# board_single_full1.net
KiCad netlist of a schematic drawn in EAGLE
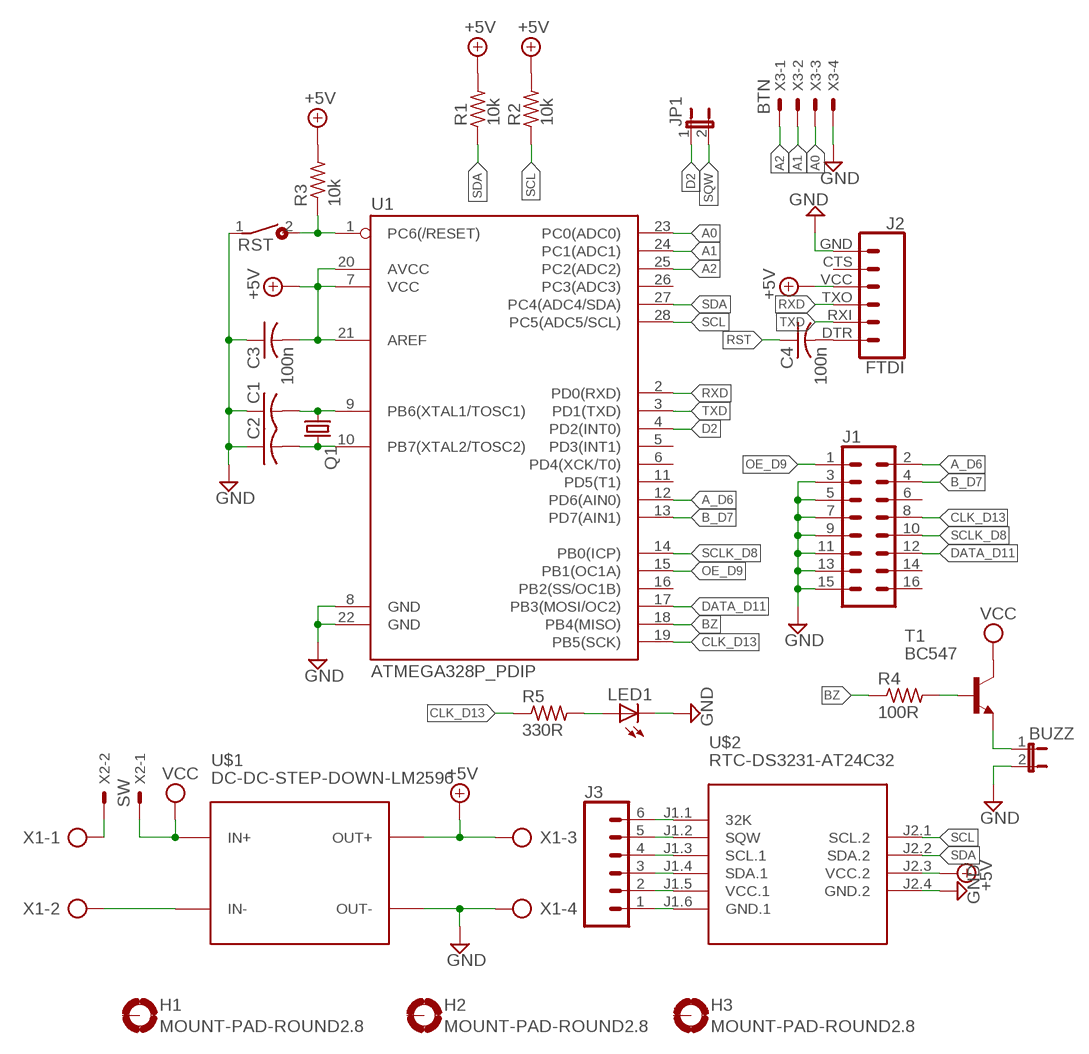
[diagram p0: schematic, sheet 1]

(export (version "E")
  (design (tool "Eeschema 10.0.6"))
  (components
    (comp (ref "BUZZ")
      (value "JP1E")
      (footprint "eagle-import:JP1")
      (libsource (lib "eagle-import") (part "JP1E"))
    )
    (comp (ref "C1")
      (value "C-USC0603K")
      (footprint "eagle-import:C0603K")
      (libsource (lib "eagle-import") (part "C-USC0603K"))
    )
    (comp (ref "C2")
      (value "C-USC0603K")
      (footprint "eagle-import:C0603K")
      (libsource (lib "eagle-import") (part "C-USC0603K"))
    )
    (comp (ref "C3")
      (value "100n")
      (footprint "eagle-import:C0603K")
      (libsource (lib "eagle-import") (part "C-USC0603K"))
    )
    (comp (ref "C4")
      (value "100n")
      (footprint "eagle-import:C0603K")
      (libsource (lib "eagle-import") (part "C-USC0603K"))
    )
    (comp (ref "H1")
      (value "MOUNT-PAD-ROUND2.8")
      (footprint "eagle-import:2,8-PAD")
      (libsource (lib "eagle-import") (part "MOUNT-PAD-ROUND2.8"))
    )
    (comp (ref "H2")
      (value "MOUNT-PAD-ROUND2.8")
      (footprint "eagle-import:2,8-PAD")
      (libsource (lib "eagle-import") (part "MOUNT-PAD-ROUND2.8"))
    )
    (comp (ref "H3")
      (value "MOUNT-PAD-ROUND2.8")
      (footprint "eagle-import:2,8-PAD")
      (libsource (lib "eagle-import") (part "MOUNT-PAD-ROUND2.8"))
    )
    (comp (ref "J1")
      (value "CONN_08X2_SHROUD")
      (footprint "eagle-import:2X8-SHROUDED_LOCK")
      (libsource (lib "eagle-import") (part "CONN_08X2_SHROUD"))
    )
    (comp (ref "J2")
      (value "FTDI")
      (footprint "eagle-import:FTDI_BASIC")
      (libsource (lib "eagle-import") (part "6_PIN_SERIAL_CABLEPTH"))
    )
    (comp (ref "J3")
      (value "CONN_06NO_SILK_FEMALE_PTH")
      (footprint "eagle-import:1X06_NO_SILK")
      (libsource (lib "eagle-import") (part "CONN_06NO_SILK_FEMALE_PTH"))
    )
    (comp (ref "JP1")
      (value "JP1E")
      (footprint "eagle-import:JP1")
      (libsource (lib "eagle-import") (part "JP1E"))
    )
    (comp (ref "LED1")
      (value "LED3MM")
      (footprint "eagle-import:LED3MM")
      (libsource (lib "eagle-import") (part "LED3MM"))
    )
    (comp (ref "Q1")
      (value "CRYSTALHC49U-V")
      (footprint "eagle-import:HC49U-V")
      (libsource (lib "eagle-import") (part "CRYSTALHC49U-V"))
    )
    (comp (ref "R1")
      (value "10k")
      (footprint "eagle-import:0207_7")
      (libsource (lib "eagle-import") (part "resistor_R-US_0207/7"))
    )
    (comp (ref "R2")
      (value "10k")
      (footprint "eagle-import:0207_7")
      (libsource (lib "eagle-import") (part "resistor_R-US_0207/7"))
    )
    (comp (ref "R3")
      (value "10k")
      (footprint "eagle-import:R0603")
      (libsource (lib "eagle-import") (part "R-US_R0603"))
    )
    (comp (ref "R4")
      (value "100R")
      (footprint "eagle-import:R0603")
      (libsource (lib "eagle-import") (part "R-US_R0603"))
    )
    (comp (ref "R5")
      (value "330R")
      (footprint "eagle-import:R0603")
      (libsource (lib "eagle-import") (part "R-US_R0603"))
    )
    (comp (ref "RST")
      (value "DS01E")
      (footprint "eagle-import:DS-01")
      (libsource (lib "eagle-import") (part "DS01E"))
    )
    (comp (ref "T1")
      (value "BC547")
      (footprint "eagle-import:TO92")
      (libsource (lib "eagle-import") (part "BC547"))
    )
    (comp (ref "U$1")
      (value "DC-DC-STEP-DOWN-LM2596")
      (footprint "eagle-import:DC-DC-STEP-DOWN-LM2596")
      (libsource (lib "eagle-import") (part "DC-DC-STEP-DOWN-LM2596"))
    )
    (comp (ref "U$2")
      (value "RTC-DS3231-AT24C32")
      (footprint "eagle-import:RTC-DS3231-AT24C32")
      (libsource (lib "eagle-import") (part "RTC-DS3231-AT24C32"))
    )
    (comp (ref "U1")
      (value "ATMEGA328P_PDIP")
      (footprint "eagle-import:DIL28-3")
      (libsource (lib "eagle-import") (part "ATMEGA328P_PDIP"))
    )
    (comp (ref "X1")
      (value "AK500/4")
      (footprint "eagle-import:AK500_4")
      (libsource (lib "eagle-import") (part "AK500/4"))
    )
    (comp (ref "X2")
      (value "SW")
      (footprint "eagle-import:JST-XH-02-PACKAGE-LONG-PAD")
      (libsource (lib "eagle-import") (part "JST-XH-02-PIN-LONG-PAD"))
    )
    (comp (ref "X3")
      (value "BTN")
      (footprint "eagle-import:JST-XH-04-PACKAGE-LONG-PAD")
      (libsource (lib "eagle-import") (part "JST-XH-04-PIN-LONG-PAD"))
    )
  )
  (nets
    (net (code "1") (name "+5V") (class "Default")
      (node (ref "C3") (pin "2") (pinfunction "2_2") (pintype "passive"))
      (node (ref "J2") (pin "VCC") (pinfunction "4_VCC") (pintype "passive"))
      (node (ref "R1") (pin "2") (pinfunction "2_2") (pintype "passive"))
      (node (ref "R2") (pin "2") (pinfunction "2_2") (pintype "passive"))
      (node (ref "R3") (pin "2") (pinfunction "2_2") (pintype "passive"))
      (node (ref "U$1") (pin "OUT+") (pinfunction "OUT+_OUT+") (pintype "bidirectional"))
      (node (ref "U$2") (pin "J2.3") (pinfunction "VCC.2_J2.3") (pintype "power_in"))
      (node (ref "U1") (pin "20") (pinfunction "AVCC_20") (pintype "bidirectional"))
      (node (ref "U1") (pin "21") (pinfunction "AREF_21") (pintype "bidirectional"))
      (node (ref "U1") (pin "7") (pinfunction "VCC_7") (pintype "bidirectional"))
      (node (ref "X1") (pin "3") (pinfunction "KL_3") (pintype "passive"))
    )
    (net (code "2") (name "A0") (class "Default")
      (node (ref "U1") (pin "23") (pinfunction "PC0(ADC0)_23") (pintype "bidirectional"))
      (node (ref "X3") (pin "3") (pinfunction "S_3") (pintype "passive"))
    )
    (net (code "3") (name "A1") (class "Default")
      (node (ref "U1") (pin "24") (pinfunction "PC1(ADC1)_24") (pintype "bidirectional"))
      (node (ref "X3") (pin "2") (pinfunction "S_2") (pintype "passive"))
    )
    (net (code "4") (name "A2") (class "Default")
      (node (ref "U1") (pin "25") (pinfunction "PC2(ADC2)_25") (pintype "bidirectional"))
      (node (ref "X3") (pin "1") (pinfunction "S_1") (pintype "passive"))
    )
    (net (code "5") (name "A_D6") (class "Default")
      (node (ref "J1") (pin "2") (pinfunction "2_2") (pintype "passive"))
      (node (ref "U1") (pin "12") (pinfunction "PD6(AIN0)_12") (pintype "bidirectional"))
    )
    (net (code "6") (name "BZ") (class "Default")
      (node (ref "R4") (pin "1") (pinfunction "1_1") (pintype "passive"))
      (node (ref "U1") (pin "18") (pinfunction "PB4(MISO)_18") (pintype "bidirectional"))
    )
    (net (code "7") (name "B_D7") (class "Default")
      (node (ref "J1") (pin "4") (pinfunction "4_4") (pintype "passive"))
      (node (ref "U1") (pin "13") (pinfunction "PD7(AIN1)_13") (pintype "bidirectional"))
    )
    (net (code "8") (name "CLK_D13") (class "Default")
      (node (ref "J1") (pin "8") (pinfunction "8_8") (pintype "passive"))
      (node (ref "R5") (pin "1") (pinfunction "1_1") (pintype "passive"))
      (node (ref "U1") (pin "19") (pinfunction "PB5(SCK)_19") (pintype "bidirectional"))
    )
    (net (code "9") (name "D2") (class "Default")
      (node (ref "JP1") (pin "1") (pinfunction "1_1") (pintype "passive"))
      (node (ref "U1") (pin "4") (pinfunction "PD2(INT0)_4") (pintype "bidirectional"))
    )
    (net (code "10") (name "DATA_D11") (class "Default")
      (node (ref "J1") (pin "12") (pinfunction "12_12") (pintype "passive"))
      (node (ref "U1") (pin "17") (pinfunction "PB3(MOSI/OC2)_17") (pintype "bidirectional"))
    )
    (net (code "11") (name "GND") (class "Default")
      (node (ref "BUZZ") (pin "2") (pinfunction "2_2") (pintype "passive"))
      (node (ref "C1") (pin "1") (pinfunction "1_1") (pintype "passive"))
      (node (ref "C2") (pin "1") (pinfunction "1_1") (pintype "passive"))
      (node (ref "C3") (pin "1") (pinfunction "1_1") (pintype "passive"))
      (node (ref "J1") (pin "11") (pinfunction "11_11") (pintype "passive"))
      (node (ref "J1") (pin "13") (pinfunction "13_13") (pintype "passive"))
      (node (ref "J1") (pin "15") (pinfunction "15_15") (pintype "passive"))
      (node (ref "J1") (pin "3") (pinfunction "3_3") (pintype "passive"))
      (node (ref "J1") (pin "5") (pinfunction "5_5") (pintype "passive"))
      (node (ref "J1") (pin "7") (pinfunction "7_7") (pintype "passive"))
      (node (ref "J1") (pin "9") (pinfunction "9_9") (pintype "passive"))
      (node (ref "J2") (pin "GND") (pinfunction "6_GND") (pintype "passive"))
      (node (ref "LED1") (pin "K") (pinfunction "C_K") (pintype "passive"))
      (node (ref "RST") (pin "1") (pinfunction "1_1") (pintype "passive"))
      (node (ref "U$1") (pin "OUT-") (pinfunction "OUT-_OUT-") (pintype "bidirectional"))
      (node (ref "U$2") (pin "J2.4") (pinfunction "GND.2_J2.4") (pintype "power_in"))
      (node (ref "U1") (pin "22") (pinfunction "GND_22") (pintype "bidirectional"))
      (node (ref "U1") (pin "8") (pinfunction "GND_8") (pintype "bidirectional"))
      (node (ref "X1") (pin "4") (pinfunction "KL_4") (pintype "passive"))
      (node (ref "X3") (pin "4") (pinfunction "S_4") (pintype "passive"))
    )
    (net (code "12") (name "Net-(J2-1)") (class "Default")
      (node (ref "C4") (pin "2") (pinfunction "2_2") (pintype "passive"))
      (node (ref "J2") (pin "DTR") (pinfunction "1_DTR") (pintype "passive"))
    )
    (net (code "13") (name "Net-(LED1-PadA)") (class "Default")
      (node (ref "LED1") (pin "A") (pinfunction "A_A") (pintype "passive"))
      (node (ref "R5") (pin "2") (pinfunction "2_2") (pintype "passive"))
    )
    (net (code "14") (name "Net-(T1-B)") (class "Default")
      (node (ref "R4") (pin "2") (pinfunction "2_2") (pintype "passive"))
      (node (ref "T1") (pin "2") (pinfunction "B_2") (pintype "passive"))
    )
    (net (code "15") (name "Net-(T1-E)") (class "Default")
      (node (ref "BUZZ") (pin "1") (pinfunction "1_1") (pintype "passive"))
      (node (ref "T1") (pin "1") (pinfunction "E_1") (pintype "passive"))
    )
    (net (code "16") (name "Net-(U$2-32K)") (class "Default")
      (node (ref "J3") (pin "6") (pinfunction "6_6") (pintype "passive"))
      (node (ref "U$2") (pin "J1.1") (pinfunction "32K_J1.1") (pintype "bidirectional"))
    )
    (net (code "17") (name "Net-(U$2-GND.1)") (class "Default")
      (node (ref "J3") (pin "1") (pinfunction "1_1") (pintype "passive"))
      (node (ref "U$2") (pin "J1.6") (pinfunction "GND.1_J1.6") (pintype "power_in"))
    )
    (net (code "18") (name "Net-(U$2-SCL.1)") (class "Default")
      (node (ref "J3") (pin "4") (pinfunction "4_4") (pintype "passive"))
      (node (ref "U$2") (pin "J1.3") (pinfunction "SCL.1_J1.3") (pintype "bidirectional"))
    )
    (net (code "19") (name "Net-(U$2-SDA.1)") (class "Default")
      (node (ref "J3") (pin "3") (pinfunction "3_3") (pintype "passive"))
      (node (ref "U$2") (pin "J1.4") (pinfunction "SDA.1_J1.4") (pintype "bidirectional"))
    )
    (net (code "20") (name "Net-(U$2-VCC.1)") (class "Default")
      (node (ref "J3") (pin "2") (pinfunction "2_2") (pintype "passive"))
      (node (ref "U$2") (pin "J1.5") (pinfunction "VCC.1_J1.5") (pintype "power_in"))
    )
    (net (code "21") (name "Net-(U1-PB6(XTAL1{slash}TOSC1))") (class "Default")
      (node (ref "C1") (pin "2") (pinfunction "2_2") (pintype "passive"))
      (node (ref "Q1") (pin "1") (pinfunction "1_1") (pintype "passive"))
      (node (ref "U1") (pin "9") (pinfunction "PB6(XTAL1/TOSC1)_9") (pintype "bidirectional"))
    )
    (net (code "22") (name "Net-(U1-PB7(XTAL2{slash}TOSC2))") (class "Default")
      (node (ref "C2") (pin "2") (pinfunction "2_2") (pintype "passive"))
      (node (ref "Q1") (pin "2") (pinfunction "2_2") (pintype "passive"))
      (node (ref "U1") (pin "10") (pinfunction "PB7(XTAL2/TOSC2)_10") (pintype "bidirectional"))
    )
    (net (code "23") (name "Net-(X1A-KL)") (class "Default")
      (node (ref "X1") (pin "1") (pinfunction "KL_1") (pintype "passive"))
      (node (ref "X2") (pin "2") (pinfunction "S_2") (pintype "passive"))
    )
    (net (code "24") (name "Net-(X1B-KL)") (class "Default")
      (node (ref "U$1") (pin "IN-") (pinfunction "IN-_IN-") (pintype "bidirectional"))
      (node (ref "X1") (pin "2") (pinfunction "KL_2") (pintype "passive"))
    )
    (net (code "25") (name "OE_D9") (class "Default")
      (node (ref "J1") (pin "1") (pinfunction "1_1") (pintype "passive"))
      (node (ref "U1") (pin "15") (pinfunction "PB1(OC1A)_15") (pintype "bidirectional"))
    )
    (net (code "26") (name "RST") (class "Default")
      (node (ref "C4") (pin "1") (pinfunction "1_1") (pintype "passive"))
      (node (ref "R3") (pin "1") (pinfunction "1_1") (pintype "passive"))
      (node (ref "RST") (pin "2") (pinfunction "2_2") (pintype "passive"))
      (node (ref "U1") (pin "1") (pinfunction "PC6(/RESET)_1") (pintype "bidirectional"))
    )
    (net (code "27") (name "RXD") (class "Default")
      (node (ref "J2") (pin "TXO") (pinfunction "3_TXO") (pintype "passive"))
      (node (ref "U1") (pin "2") (pinfunction "PD0(RXD)_2") (pintype "bidirectional"))
    )
    (net (code "28") (name "SCL") (class "Default")
      (node (ref "R2") (pin "1") (pinfunction "1_1") (pintype "passive"))
      (node (ref "U$2") (pin "J2.1") (pinfunction "SCL.2_J2.1") (pintype "bidirectional"))
      (node (ref "U1") (pin "28") (pinfunction "PC5(ADC5/SCL)_28") (pintype "bidirectional"))
    )
    (net (code "29") (name "SCLK_D8") (class "Default")
      (node (ref "J1") (pin "10") (pinfunction "10_10") (pintype "passive"))
      (node (ref "U1") (pin "14") (pinfunction "PB0(ICP)_14") (pintype "bidirectional"))
    )
    (net (code "30") (name "SDA") (class "Default")
      (node (ref "R1") (pin "1") (pinfunction "1_1") (pintype "passive"))
      (node (ref "U$2") (pin "J2.2") (pinfunction "SDA.2_J2.2") (pintype "bidirectional"))
      (node (ref "U1") (pin "27") (pinfunction "PC4(ADC4/SDA)_27") (pintype "bidirectional"))
    )
    (net (code "31") (name "SQW") (class "Default")
      (node (ref "J3") (pin "5") (pinfunction "5_5") (pintype "passive"))
      (node (ref "JP1") (pin "2") (pinfunction "2_2") (pintype "passive"))
      (node (ref "U$2") (pin "J1.2") (pinfunction "SQW_J1.2") (pintype "bidirectional"))
    )
    (net (code "32") (name "TXD") (class "Default")
      (node (ref "J2") (pin "RXI") (pinfunction "2_RXI") (pintype "passive"))
      (node (ref "U1") (pin "3") (pinfunction "PD1(TXD)_3") (pintype "bidirectional"))
    )
    (net (code "33") (name "VCC") (class "Default")
      (node (ref "T1") (pin "3") (pinfunction "C_3") (pintype "passive"))
      (node (ref "U$1") (pin "IN+") (pinfunction "IN+_IN+") (pintype "bidirectional"))
      (node (ref "X2") (pin "1") (pinfunction "S_1") (pintype "passive"))
    )
    (net (code "34") (name "unconnected-(H1-MOUNT-PadB2,8)") (class "Default")
      (node (ref "H1") (pin "B2,8") (pinfunction "MOUNT_B2,8") (pintype "passive"))
    )
    (net (code "35") (name "unconnected-(H2-MOUNT-PadB2,8)") (class "Default")
      (node (ref "H2") (pin "B2,8") (pinfunction "MOUNT_B2,8") (pintype "passive"))
    )
    (net (code "36") (name "unconnected-(H3-MOUNT-PadB2,8)") (class "Default")
      (node (ref "H3") (pin "B2,8") (pinfunction "MOUNT_B2,8") (pintype "passive"))
    )
    (net (code "37") (name "unconnected-(J1-Pad6)") (class "Default")
      (node (ref "J1") (pin "6") (pinfunction "6_6") (pintype "passive"))
    )
    (net (code "38") (name "unconnected-(J1-Pad14)") (class "Default")
      (node (ref "J1") (pin "14") (pinfunction "14_14") (pintype "passive"))
    )
    (net (code "39") (name "unconnected-(J1-Pad16)") (class "Default")
      (node (ref "J1") (pin "16") (pinfunction "16_16") (pintype "passive"))
    )
    (net (code "40") (name "unconnected-(J2-5-PadCTS)") (class "Default")
      (node (ref "J2") (pin "CTS") (pinfunction "5_CTS") (pintype "passive"))
    )
    (net (code "41") (name "unconnected-(U1-PB2(SS{slash}OC1B)-Pad16)") (class "Default")
      (node (ref "U1") (pin "16") (pinfunction "PB2(SS/OC1B)_16") (pintype "bidirectional"))
    )
    (net (code "42") (name "unconnected-(U1-PC3(ADC3)-Pad26)") (class "Default")
      (node (ref "U1") (pin "26") (pinfunction "PC3(ADC3)_26") (pintype "bidirectional"))
    )
    (net (code "43") (name "unconnected-(U1-PD3(INT1)-Pad5)") (class "Default")
      (node (ref "U1") (pin "5") (pinfunction "PD3(INT1)_5") (pintype "bidirectional"))
    )
    (net (code "44") (name "unconnected-(U1-PD4(XCK{slash}T0)-Pad6)") (class "Default")
      (node (ref "U1") (pin "6") (pinfunction "PD4(XCK/T0)_6") (pintype "bidirectional"))
    )
    (net (code "45") (name "unconnected-(U1-PD5(T1)-Pad11)") (class "Default")
      (node (ref "U1") (pin "11") (pinfunction "PD5(T1)_11") (pintype "bidirectional"))
    )
  )
)
